# ESP32RobotBoard.net
KiCad netlist of a schematic drawn in Altium Designer
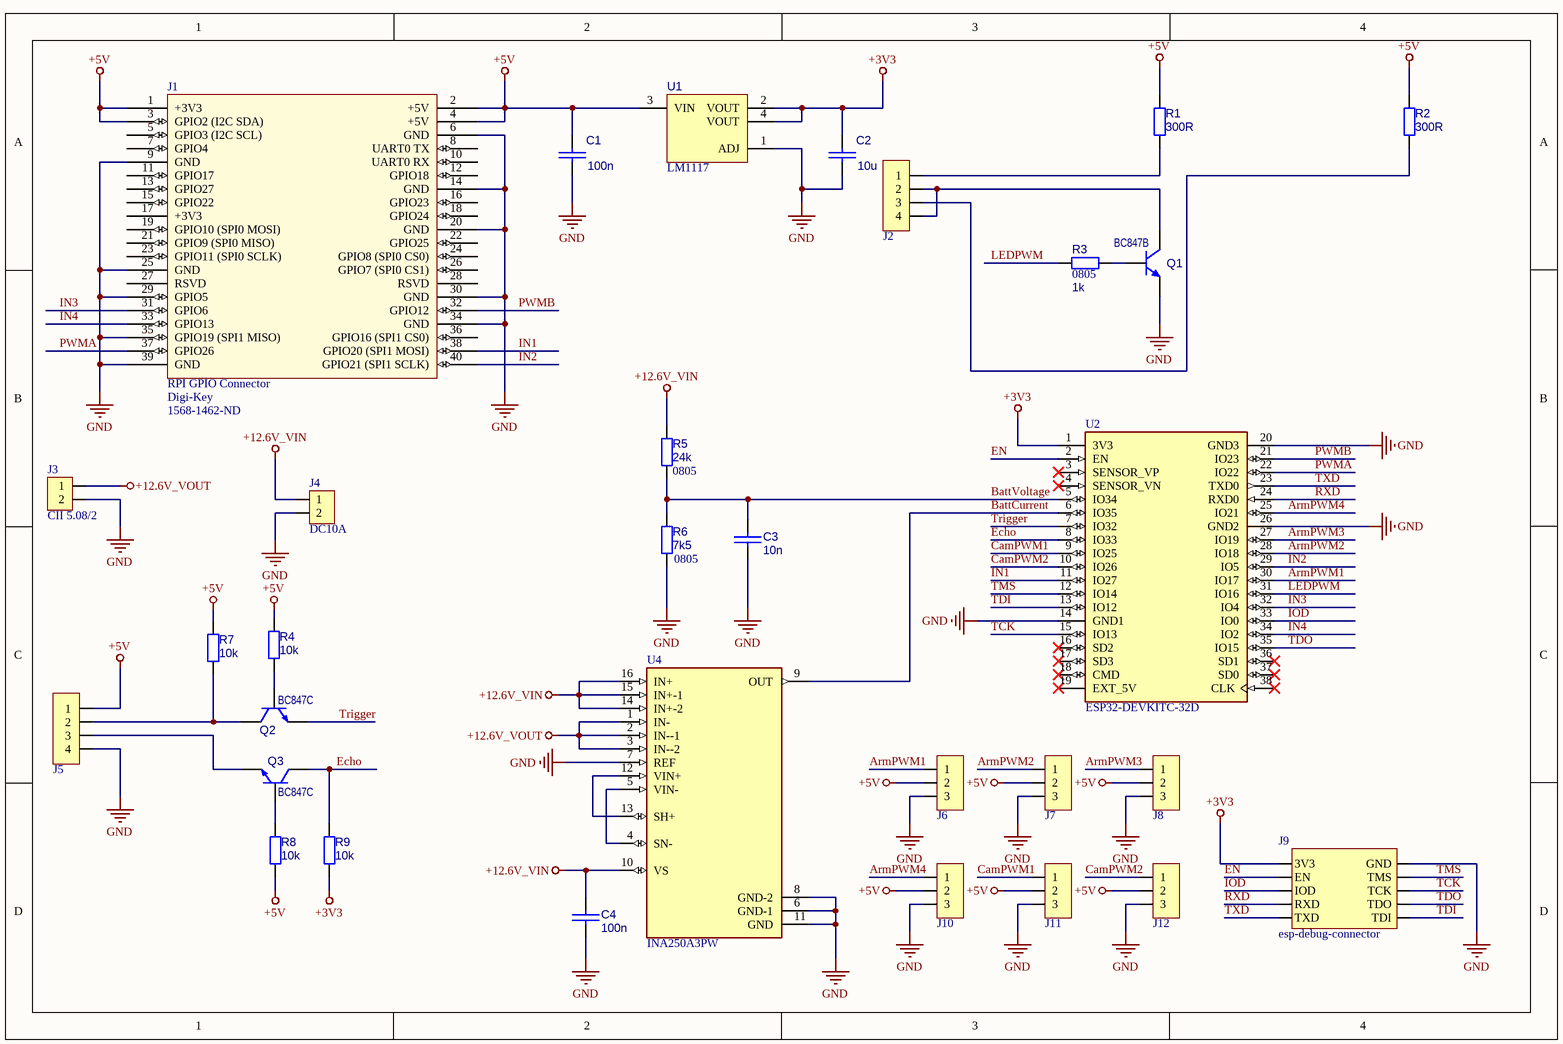
[diagram p0: ESP32RobotBoard.SchDoc]

(export (version "E")
  (design (tool "Eeschema 10.0.6"))
  (components
    (comp (ref "C1")
      (value "100n")
      (footprint "TandariPcbLib:C0805")
      (description "Ceramic Chip Capacitor 0805 size")
      (fields (field (name "VOLTAGE") "50V") (field (name "MANUFACTURER") "NIC COMPONENTS"))
      (libsource (lib "TandariSchlib") (part "Cap100n_50V_0805"))
    )
    (comp (ref "C2")
      (value "10u")
      (footprint "TandariPcbLib:C0805")
      (description "Ceramic Chip Capacitor 0805 size")
      (fields (field (name "VOLTAGE") "10V") (field (name "MANUFACTURER") "NIC"))
      (libsource (lib "TandariSchlib") (part "Cap10u_10V_0805"))
    )
    (comp (ref "C3")
      (value "10n")
      (footprint "TandariPcbLib:C0805")
      (description "Ceramic Chip Capacitor 0805 size")
      (fields (field (name "VOLTAGE") "50V") (field (name "MANUFACTURER") "NIC COMPONENTS"))
      (libsource (lib "TandariSchlib") (part "Cap10n_50V_0805"))
    )
    (comp (ref "C4")
      (value "100n")
      (footprint "TandariPcbLib:C0805")
      (description "Ceramic Chip Capacitor 0805 size")
      (fields (field (name "VOLTAGE") "50V") (field (name "MANUFACTURER") "NIC COMPONENTS"))
      (libsource (lib "TandariSchlib") (part "Cap100n_50V_0805"))
    )
    (comp (ref "J1")
      (value "RPI GPIO Connector")
      (footprint "rpi")
      (description "GPIO Header for Raspberry Pi A+/B+/Pi 2/Pi 3 - 2x20")
      (fields
        (field (name "MANUFACTURER") "SparkFun Electronics")
        (field (name "MANUFACTURER PART NUMBER") "PRT-14017")
        (field (name "SUPPLIER 1") "Digi-Key")
        (field (name "SUPPLIER PART NUMBER 1") "1568-1462-ND")
      )
      (libsource (lib "rpi") (part "rpi connector"))
    )
    (comp (ref "J2")
      (value "BUCHSEHN_1X4")
      (footprint "MKDSN2,5/4-5,08")
      (description "1X4_HEADER")
      (fields (field (name "MANUFACTURER") "E-TEC"))
      (libsource (lib "TandariSchlib") (part "BUCHSEHN_1X4"))
    )
    (comp (ref "J3")
      (value "CII 5.08/2")
      (footprint "MKDSN2,5/2-5,08")
      (fields (field (name "MANUFACTURER") "STELVIO") (field (name "Comment") "2X1Molex"))
      (libsource (lib "TandariSchlib") (part "2X1Molex"))
    )
    (comp (ref "J4")
      (value "DC10A")
      (footprint "DC10A")
      (description "DC 10A connector")
      (fields (field (name "MANUFACTURER") "CLIFF") (field (name "Comment") "CONN_DC10A"))
      (libsource (lib "TandariSchlib") (part "CONN_DC10A"))
    )
    (comp (ref "J5")
      (value "BUCHSEHN_1X4")
      (footprint "MKDSN2,5/4-5,08")
      (description "1X4_HEADER")
      (fields (field (name "MANUFACTURER") "E-TEC"))
      (libsource (lib "TandariSchlib") (part "BUCHSEHN_1X4"))
    )
    (comp (ref "J6")
      (value "BUCHSEHN_1X3")
      (footprint "TandariPcbLib:HEADER_3X1 - male")
      (description "1X3_HEADER")
      (fields (field (name "MANUFACTURER") "E-TEC"))
      (libsource (lib "TandariSchlib") (part "BUCHSEHN_1X3"))
    )
    (comp (ref "J7")
      (value "BUCHSEHN_1X3")
      (footprint "TandariPcbLib:HEADER_3X1 - male")
      (description "1X3_HEADER")
      (fields (field (name "MANUFACTURER") "E-TEC"))
      (libsource (lib "TandariSchlib") (part "BUCHSEHN_1X3"))
    )
    (comp (ref "J8")
      (value "BUCHSEHN_1X3")
      (footprint "TandariPcbLib:HEADER_3X1 - male")
      (description "1X3_HEADER")
      (fields (field (name "MANUFACTURER") "E-TEC"))
      (libsource (lib "TandariSchlib") (part "BUCHSEHN_1X3"))
    )
    (comp (ref "J9")
      (value "esp-debug-connector")
      (footprint "SAMTEC-FTS-105-01-X-DV")
      (fields (field (name "PART NUMBER") "53-04-57"))
      (libsource (lib "TandariSchlib") (part "esp-debug-connector"))
    )
    (comp (ref "J10")
      (value "BUCHSEHN_1X3")
      (footprint "TandariPcbLib:HEADER_3X1 - male")
      (description "1X3_HEADER")
      (fields (field (name "MANUFACTURER") "E-TEC"))
      (libsource (lib "TandariSchlib") (part "BUCHSEHN_1X3"))
    )
    (comp (ref "J11")
      (value "BUCHSEHN_1X3")
      (footprint "TandariPcbLib:HEADER_3X1 - male")
      (description "1X3_HEADER")
      (fields (field (name "MANUFACTURER") "E-TEC"))
      (libsource (lib "TandariSchlib") (part "BUCHSEHN_1X3"))
    )
    (comp (ref "J12")
      (value "BUCHSEHN_1X3")
      (footprint "TandariPcbLib:HEADER_3X1 - male")
      (description "1X3_HEADER")
      (fields (field (name "MANUFACTURER") "E-TEC"))
      (libsource (lib "TandariSchlib") (part "BUCHSEHN_1X3"))
    )
    (comp (ref "Q1")
      (value "NPN")
      (footprint "SOT23-3")
      (description "NPN small-signal 100mA 45V 250mW SOT-23")
      (fields (field (name "MANUFACTURER") "ON Semi") (field (name "PARTNUMBER") "BC847B"))
      (libsource (lib "TandariSchlib") (part "NPN"))
    )
    (comp (ref "Q2")
      (value "BC847C")
      (footprint "TandariPcbLib:SOT23-3")
      (description "NPN Bipolar transistor 100mA 45V UCE")
      (fields (field (name "MANUFACTURER") "NXP") (field (name "Comment") "BC847C_SOT23"))
      (libsource (lib "TandariSchlib") (part "BC847C_SOT23"))
    )
    (comp (ref "Q3")
      (value "BC847C")
      (footprint "TandariPcbLib:SOT23-3")
      (description "NPN Bipolar transistor 100mA 45V UCE")
      (fields (field (name "MANUFACTURER") "NXP") (field (name "Comment") "BC847C_SOT23"))
      (libsource (lib "TandariSchlib") (part "BC847C_SOT23"))
    )
    (comp (ref "R1")
      (value "300R")
      (footprint "TandariPcbLib:R0805")
      (description "Chip Resistor Thick Film")
      (fields (field (name "POWER") "125mW") (field (name "MANUFACTURER") "YAGEO"))
      (libsource (lib "") (part "Res300R_125mW_0805_1"))
    )
    (comp (ref "R2")
      (value "300R")
      (footprint "TandariPcbLib:R0805")
      (description "Chip Resistor Thick Film")
      (fields (field (name "POWER") "125mW") (field (name "MANUFACTURER") "YAGEO"))
      (libsource (lib "TandariSchlib") (part "Res300R_125mW_0805"))
    )
    (comp (ref "R3")
      (value "1k")
      (footprint "TandariPcbLib:R0805")
      (description "Chip Resistor Thick Film")
      (fields
        (field (name "POWER") "125mW")
        (field (name "MANUFACTURER") "YAGEO")
        (field (name "PACKAGE") "0805")
      )
      (libsource (lib "TandariSchlib") (part "Res1k_125mW_0805"))
    )
    (comp (ref "R4")
      (value "10k")
      (footprint "TandariPcbLib:R0805")
      (description "Chip Resistor Thick Film")
      (fields (field (name "POWER") "125mW") (field (name "MANUFACTURER") "YAGEO"))
      (libsource (lib "TandariSchlib") (part "Res10k_125mW_0805"))
    )
    (comp (ref "R5")
      (value "24k")
      (footprint "TandariPcbLib:R0805")
      (description "Chip Resistor Thick Film")
      (fields
        (field (name "POWER") "125mW")
        (field (name "MANUFACTURER") "YAGEO")
        (field (name "PACKAGE") "0805")
      )
      (libsource (lib "TandariSchlib") (part "Res24k_125mW_0805"))
    )
    (comp (ref "R6")
      (value "7k5")
      (footprint "TandariPcbLib:R0805")
      (description "Chip Resistor Thick Film")
      (fields
        (field (name "POWER") "125mW")
        (field (name "MANUFACTURER") "YAGEO")
        (field (name "PACKAGE") "0805")
      )
      (libsource (lib "TandariSchlib") (part "Res7k5_125mW_0805"))
    )
    (comp (ref "R7")
      (value "10k")
      (footprint "TandariPcbLib:R0805")
      (description "Chip Resistor Thick Film")
      (fields (field (name "POWER") "125mW") (field (name "MANUFACTURER") "YAGEO"))
      (libsource (lib "TandariSchlib") (part "Res10k_125mW_0805"))
    )
    (comp (ref "R8")
      (value "10k")
      (footprint "TandariPcbLib:R0805")
      (description "Chip Resistor Thick Film")
      (fields (field (name "POWER") "125mW") (field (name "MANUFACTURER") "YAGEO"))
      (libsource (lib "TandariSchlib") (part "Res10k_125mW_0805"))
    )
    (comp (ref "R9")
      (value "10k")
      (footprint "TandariPcbLib:R0805")
      (description "Chip Resistor Thick Film")
      (fields (field (name "POWER") "125mW") (field (name "MANUFACTURER") "YAGEO"))
      (libsource (lib "TandariSchlib") (part "Res10k_125mW_0805"))
    )
    (comp (ref "U1")
      (value "LM1117")
      (footprint "SOT223")
      (description "15V 800mA adjustable LDO SOT-223")
      (fields (field (name "MANUFACTURER") "National Semiconductor"))
      (libsource (lib "TandariSchlib") (part "LM1117-ADJ"))
    )
    (comp (ref "U2")
      (value "ESP32-DEVKITC-32D")
      (footprint "Espressif_Systems_ESP32-WROOM-32D_MFG")
      (description "EVAL BOARD FOR ESP-WROOM-32")
      (fields (field (name "MF") "Espressif Systems"))
      (libsource (lib "TandariSchlib") (part "ESP32-DEVKITC-32D"))
    )
    (comp (ref "U4")
      (value "INA250A3PW")
      (footprint "TSSOP-16")
      (description "36V, bi-directional, precision current sense amplifier w/int. shunt resistor 16-TSSOP -40 to 125")
      (fields (field (name "MF") "Texas Instruments"))
      (libsource (lib "TandariSchlib") (part "INA250A3PW"))
    )
  )
  (nets
    (net (code "1") (name "+3V3") (class "Default")
      (node (ref "C2") (pin "1") (pinfunction "1_1") (pintype "passive"))
      (node (ref "J9") (pin "1") (pinfunction "3V3_1") (pintype "passive"))
      (node (ref "R9") (pin "1") (pinfunction "1_1") (pintype "passive"))
      (node (ref "U1") (pin "2") (pinfunction "VOUT_2") (pintype "passive"))
      (node (ref "U1") (pin "4") (pinfunction "VOUT_4") (pintype "passive"))
      (node (ref "U2") (pin "1") (pinfunction "3V3_1") (pintype "power_in"))
    )
    (net (code "2") (name "+5V") (class "Default")
      (node (ref "C1") (pin "1") (pinfunction "1_1") (pintype "passive"))
      (node (ref "J1") (pin "1") (pinfunction "+3V3_1") (pintype "power_in"))
      (node (ref "J1") (pin "2") (pinfunction "+5V_2") (pintype "power_in"))
      (node (ref "J1") (pin "3") (pinfunction "GPIO2_(I2C_SDA)_3") (pintype "bidirectional"))
      (node (ref "J1") (pin "4") (pinfunction "+5V_4") (pintype "power_in"))
      (node (ref "J10") (pin "2") (pinfunction "2_2") (pintype "passive"))
      (node (ref "J11") (pin "2") (pinfunction "2_2") (pintype "passive"))
      (node (ref "J12") (pin "2") (pinfunction "2_2") (pintype "passive"))
      (node (ref "J5") (pin "1") (pinfunction "1_1") (pintype "passive"))
      (node (ref "J6") (pin "2") (pinfunction "2_2") (pintype "passive"))
      (node (ref "J7") (pin "2") (pinfunction "2_2") (pintype "passive"))
      (node (ref "J8") (pin "2") (pinfunction "2_2") (pintype "passive"))
      (node (ref "R1") (pin "2") (pinfunction "2_2") (pintype "passive"))
      (node (ref "R2") (pin "2") (pinfunction "2_2") (pintype "passive"))
      (node (ref "R4") (pin "2") (pinfunction "2_2") (pintype "passive"))
      (node (ref "R7") (pin "2") (pinfunction "2_2") (pintype "passive"))
      (node (ref "R8") (pin "1") (pinfunction "1_1") (pintype "passive"))
      (node (ref "U1") (pin "3") (pinfunction "VIN_3") (pintype "passive"))
    )
    (net (code "3") (name "+12.6V_VIN") (class "Default")
      (node (ref "C4") (pin "1") (pinfunction "1_1") (pintype "passive"))
      (node (ref "J4") (pin "1") (pinfunction "1_1") (pintype "passive"))
      (node (ref "R5") (pin "2") (pinfunction "2_2") (pintype "passive"))
      (node (ref "U4") (pin "10") (pinfunction "VS_10") (pintype "bidirectional"))
      (node (ref "U4") (pin "14") (pinfunction "IN+-2_14") (pintype "input"))
      (node (ref "U4") (pin "15") (pinfunction "IN+-1_15") (pintype "input"))
      (node (ref "U4") (pin "16") (pinfunction "IN+_16") (pintype "input"))
    )
    (net (code "4") (name "+12.6V_VOUT") (class "Default")
      (node (ref "J3") (pin "1") (pinfunction "1_1") (pintype "passive"))
      (node (ref "U4") (pin "1") (pinfunction "IN-_1") (pintype "input"))
      (node (ref "U4") (pin "2") (pinfunction "IN--1_2") (pintype "input"))
      (node (ref "U4") (pin "3") (pinfunction "IN--2_3") (pintype "input"))
    )
    (net (code "5") (name "/ArmPWM1") (class "Default")
      (node (ref "J6") (pin "1") (pinfunction "1_1") (pintype "passive"))
      (node (ref "U2") (pin "30") (pinfunction "IO17_30") (pintype "bidirectional"))
    )
    (net (code "6") (name "/ArmPWM2") (class "Default")
      (node (ref "J7") (pin "1") (pinfunction "1_1") (pintype "passive"))
      (node (ref "U2") (pin "28") (pinfunction "IO18_28") (pintype "bidirectional"))
    )
    (net (code "7") (name "/ArmPWM3") (class "Default")
      (node (ref "J8") (pin "1") (pinfunction "1_1") (pintype "passive"))
      (node (ref "U2") (pin "27") (pinfunction "IO19_27") (pintype "bidirectional"))
    )
    (net (code "8") (name "/ArmPWM4") (class "Default")
      (node (ref "J10") (pin "1") (pinfunction "1_1") (pintype "passive"))
      (node (ref "U2") (pin "25") (pinfunction "IO21_25") (pintype "bidirectional"))
    )
    (net (code "9") (name "/BattCurrent") (class "Default")
      (node (ref "U2") (pin "6") (pinfunction "IO35_6") (pintype "bidirectional"))
      (node (ref "U4") (pin "9") (pinfunction "OUT_9") (pintype "output"))
    )
    (net (code "10") (name "/BattVoltage") (class "Default")
      (node (ref "C3") (pin "1") (pinfunction "1_1") (pintype "passive"))
      (node (ref "R5") (pin "1") (pinfunction "1_1") (pintype "passive"))
      (node (ref "R6") (pin "2") (pinfunction "2_2") (pintype "passive"))
      (node (ref "U2") (pin "5") (pinfunction "IO34_5") (pintype "bidirectional"))
    )
    (net (code "11") (name "/CamPWM1") (class "Default")
      (node (ref "J11") (pin "1") (pinfunction "1_1") (pintype "passive"))
      (node (ref "U2") (pin "9") (pinfunction "IO25_9") (pintype "bidirectional"))
    )
    (net (code "12") (name "/CamPWM2") (class "Default")
      (node (ref "J12") (pin "1") (pinfunction "1_1") (pintype "passive"))
      (node (ref "U2") (pin "10") (pinfunction "IO26_10") (pintype "bidirectional"))
    )
    (net (code "13") (name "/EN") (class "Default")
      (node (ref "J9") (pin "3") (pinfunction "EN_3") (pintype "passive"))
      (node (ref "U2") (pin "2") (pinfunction "EN_2") (pintype "input"))
    )
    (net (code "14") (name "/Echo") (class "Default")
      (node (ref "Q3") (pin "3") (pinfunction "C_3") (pintype "passive"))
      (node (ref "R9") (pin "2") (pinfunction "2_2") (pintype "passive"))
      (node (ref "U2") (pin "8") (pinfunction "IO33_8") (pintype "bidirectional"))
    )
    (net (code "15") (name "/IN1") (class "Default")
      (node (ref "J1") (pin "38") (pinfunction "GPIO20_(SPI1_MOSI)_38") (pintype "bidirectional"))
      (node (ref "U2") (pin "11") (pinfunction "IO27_11") (pintype "bidirectional"))
    )
    (net (code "16") (name "/IN2") (class "Default")
      (node (ref "J1") (pin "40") (pinfunction "GPIO21_(SPI1_SCLK)_40") (pintype "bidirectional"))
      (node (ref "U2") (pin "29") (pinfunction "IO5_29") (pintype "bidirectional"))
    )
    (net (code "17") (name "/IN3") (class "Default")
      (node (ref "J1") (pin "31") (pinfunction "GPIO6_31") (pintype "bidirectional"))
      (node (ref "U2") (pin "32") (pinfunction "IO4_32") (pintype "bidirectional"))
    )
    (net (code "18") (name "/IN4") (class "Default")
      (node (ref "J1") (pin "33") (pinfunction "GPIO13_33") (pintype "bidirectional"))
      (node (ref "U2") (pin "34") (pinfunction "IO2_34") (pintype "bidirectional"))
    )
    (net (code "19") (name "/IOD") (class "Default")
      (node (ref "J9") (pin "5") (pinfunction "IOD_5") (pintype "passive"))
      (node (ref "U2") (pin "33") (pinfunction "IO0_33") (pintype "bidirectional"))
    )
    (net (code "20") (name "/LEDPWM") (class "Default")
      (node (ref "R3") (pin "1") (pinfunction "1_1") (pintype "passive"))
      (node (ref "U2") (pin "31") (pinfunction "IO16_31") (pintype "bidirectional"))
    )
    (net (code "21") (name "/PWMA") (class "Default")
      (node (ref "J1") (pin "37") (pinfunction "GPIO26_37") (pintype "bidirectional"))
      (node (ref "U2") (pin "22") (pinfunction "IO22_22") (pintype "bidirectional"))
    )
    (net (code "22") (name "/PWMB") (class "Default")
      (node (ref "J1") (pin "32") (pinfunction "GPIO12_32") (pintype "bidirectional"))
      (node (ref "U2") (pin "21") (pinfunction "IO23_21") (pintype "bidirectional"))
    )
    (net (code "23") (name "/RXD") (class "Default")
      (node (ref "J9") (pin "7") (pinfunction "RXD_7") (pintype "passive"))
      (node (ref "U2") (pin "24") (pinfunction "RXD0_24") (pintype "input"))
    )
    (net (code "24") (name "/TCK") (class "Default")
      (node (ref "J9") (pin "6") (pinfunction "TCK_6") (pintype "passive"))
      (node (ref "U2") (pin "15") (pinfunction "IO13_15") (pintype "bidirectional"))
    )
    (net (code "25") (name "/TDI") (class "Default")
      (node (ref "J9") (pin "10") (pinfunction "TDI_10") (pintype "passive"))
      (node (ref "U2") (pin "13") (pinfunction "IO12_13") (pintype "bidirectional"))
    )
    (net (code "26") (name "/TDO") (class "Default")
      (node (ref "J9") (pin "8") (pinfunction "TDO_8") (pintype "passive"))
      (node (ref "U2") (pin "35") (pinfunction "IO15_35") (pintype "bidirectional"))
    )
    (net (code "27") (name "/TMS") (class "Default")
      (node (ref "J9") (pin "4") (pinfunction "TMS_4") (pintype "passive"))
      (node (ref "U2") (pin "12") (pinfunction "IO14_12") (pintype "bidirectional"))
    )
    (net (code "28") (name "/TXD") (class "Default")
      (node (ref "J9") (pin "9") (pinfunction "TXD_9") (pintype "passive"))
      (node (ref "U2") (pin "23") (pinfunction "TXD0_23") (pintype "output"))
    )
    (net (code "29") (name "/Trigger") (class "Default")
      (node (ref "Q2") (pin "2") (pinfunction "E_2") (pintype "passive"))
      (node (ref "U2") (pin "7") (pinfunction "IO32_7") (pintype "bidirectional"))
    )
    (net (code "30") (name "GND") (class "Default")
      (node (ref "C1") (pin "2") (pinfunction "2_2") (pintype "passive"))
      (node (ref "C2") (pin "2") (pinfunction "2_2") (pintype "passive"))
      (node (ref "C3") (pin "2") (pinfunction "2_2") (pintype "passive"))
      (node (ref "C4") (pin "2") (pinfunction "2_2") (pintype "passive"))
      (node (ref "J1") (pin "14") (pinfunction "GND_14") (pintype "power_in"))
      (node (ref "J1") (pin "20") (pinfunction "GND_20") (pintype "power_in"))
      (node (ref "J1") (pin "25") (pinfunction "GND_25") (pintype "power_in"))
      (node (ref "J1") (pin "29") (pinfunction "GPIO5_29") (pintype "bidirectional"))
      (node (ref "J1") (pin "30") (pinfunction "GND_30") (pintype "power_in"))
      (node (ref "J1") (pin "34") (pinfunction "GND_34") (pintype "passive"))
      (node (ref "J1") (pin "35") (pinfunction "GPIO19_(SPI1_MISO)_35") (pintype "bidirectional"))
      (node (ref "J1") (pin "39") (pinfunction "GND_39") (pintype "power_in"))
      (node (ref "J1") (pin "6") (pinfunction "GND_6") (pintype "power_in"))
      (node (ref "J1") (pin "9") (pinfunction "GND_9") (pintype "power_in"))
      (node (ref "J10") (pin "3") (pinfunction "3_3") (pintype "passive"))
      (node (ref "J11") (pin "3") (pinfunction "3_3") (pintype "passive"))
      (node (ref "J12") (pin "3") (pinfunction "3_3") (pintype "passive"))
      (node (ref "J3") (pin "2") (pinfunction "2_2") (pintype "passive"))
      (node (ref "J4") (pin "2") (pinfunction "2_2") (pintype "passive"))
      (node (ref "J5") (pin "4") (pinfunction "4_4") (pintype "passive"))
      (node (ref "J6") (pin "3") (pinfunction "3_3") (pintype "passive"))
      (node (ref "J7") (pin "3") (pinfunction "3_3") (pintype "passive"))
      (node (ref "J8") (pin "3") (pinfunction "3_3") (pintype "passive"))
      (node (ref "J9") (pin "2") (pinfunction "GND_2") (pintype "passive"))
      (node (ref "Q1") (pin "2") (pinfunction "E_2") (pintype "passive"))
      (node (ref "R6") (pin "1") (pinfunction "1_1") (pintype "passive"))
      (node (ref "U1") (pin "1") (pinfunction "ADJ_1") (pintype "passive"))
      (node (ref "U2") (pin "14") (pinfunction "GND1_14") (pintype "power_in"))
      (node (ref "U2") (pin "20") (pinfunction "GND3_20") (pintype "power_in"))
      (node (ref "U2") (pin "26") (pinfunction "GND2_26") (pintype "power_in"))
      (node (ref "U4") (pin "11") (pinfunction "GND_11") (pintype "power_in"))
      (node (ref "U4") (pin "6") (pinfunction "GND-1_6") (pintype "power_in"))
      (node (ref "U4") (pin "7") (pinfunction "REF_7") (pintype "input"))
      (node (ref "U4") (pin "8") (pinfunction "GND-2_8") (pintype "power_in"))
    )
    (net (code "31") (name "Net-(J2-Pad1)") (class "Default")
      (node (ref "J2") (pin "1") (pinfunction "1_1") (pintype "passive"))
      (node (ref "R1") (pin "1") (pinfunction "1_1") (pintype "passive"))
    )
    (net (code "32") (name "Net-(J2-Pad3)") (class "Default")
      (node (ref "J2") (pin "3") (pinfunction "3_3") (pintype "passive"))
      (node (ref "R2") (pin "1") (pinfunction "1_1") (pintype "passive"))
    )
    (net (code "33") (name "Net-(Q1-B)") (class "Default")
      (node (ref "Q1") (pin "1") (pinfunction "B_1") (pintype "passive"))
      (node (ref "R3") (pin "2") (pinfunction "2_2") (pintype "passive"))
    )
    (net (code "34") (name "Net-(Q1-C)") (class "Default")
      (node (ref "J2") (pin "2") (pinfunction "2_2") (pintype "passive"))
      (node (ref "J2") (pin "4") (pinfunction "4_4") (pintype "passive"))
      (node (ref "Q1") (pin "3") (pinfunction "C_3") (pintype "passive"))
    )
    (net (code "35") (name "Net-(Q2-B)") (class "Default")
      (node (ref "Q2") (pin "1") (pinfunction "B_1") (pintype "passive"))
      (node (ref "R4") (pin "1") (pinfunction "1_1") (pintype "passive"))
    )
    (net (code "36") (name "Net-(Q2-C)") (class "Default")
      (node (ref "J5") (pin "2") (pinfunction "2_2") (pintype "passive"))
      (node (ref "Q2") (pin "3") (pinfunction "C_3") (pintype "passive"))
      (node (ref "R7") (pin "1") (pinfunction "1_1") (pintype "passive"))
    )
    (net (code "37") (name "Net-(Q3-B)") (class "Default")
      (node (ref "Q3") (pin "1") (pinfunction "B_1") (pintype "passive"))
      (node (ref "R8") (pin "2") (pinfunction "2_2") (pintype "passive"))
    )
    (net (code "38") (name "Net-(Q3-E)") (class "Default")
      (node (ref "J5") (pin "3") (pinfunction "3_3") (pintype "passive"))
      (node (ref "Q3") (pin "2") (pinfunction "E_2") (pintype "passive"))
    )
    (net (code "39") (name "Net-(U4-SH+)") (class "Default")
      (node (ref "U4") (pin "12") (pinfunction "VIN+_12") (pintype "input"))
      (node (ref "U4") (pin "13") (pinfunction "SH+_13") (pintype "bidirectional"))
    )
    (net (code "40") (name "Net-(U4-SN-)") (class "Default")
      (node (ref "U4") (pin "4") (pinfunction "SN-_4") (pintype "bidirectional"))
      (node (ref "U4") (pin "5") (pinfunction "VIN-_5") (pintype "input"))
    )
    (net (code "41") (name "unconnected-(J1-+3V3-Pad17)") (class "Default")
      (node (ref "J1") (pin "17") (pinfunction "+3V3_17") (pintype "power_in"))
    )
    (net (code "42") (name "unconnected-(J1-GPIO3_(I2C_SCL)-Pad5)") (class "Default")
      (node (ref "J1") (pin "5") (pinfunction "GPIO3_(I2C_SCL)_5") (pintype "bidirectional"))
    )
    (net (code "43") (name "unconnected-(J1-GPIO4-Pad7)") (class "Default")
      (node (ref "J1") (pin "7") (pinfunction "GPIO4_7") (pintype "bidirectional"))
    )
    (net (code "44") (name "unconnected-(J1-GPIO7_(SPI0_CS1)-Pad26)") (class "Default")
      (node (ref "J1") (pin "26") (pinfunction "GPIO7_(SPI0_CS1)_26") (pintype "bidirectional"))
    )
    (net (code "45") (name "unconnected-(J1-GPIO8_(SPI0_CS0)-Pad24)") (class "Default")
      (node (ref "J1") (pin "24") (pinfunction "GPIO8_(SPI0_CS0)_24") (pintype "bidirectional"))
    )
    (net (code "46") (name "unconnected-(J1-GPIO9_(SPI0_MISO)-Pad21)") (class "Default")
      (node (ref "J1") (pin "21") (pinfunction "GPIO9_(SPI0_MISO)_21") (pintype "bidirectional"))
    )
    (net (code "47") (name "unconnected-(J1-GPIO10_(SPI0_MOSI)-Pad19)") (class "Default")
      (node (ref "J1") (pin "19") (pinfunction "GPIO10_(SPI0_MOSI)_19") (pintype "bidirectional"))
    )
    (net (code "48") (name "unconnected-(J1-GPIO11_(SPI0_SCLK)-Pad23)") (class "Default")
      (node (ref "J1") (pin "23") (pinfunction "GPIO11_(SPI0_SCLK)_23") (pintype "bidirectional"))
    )
    (net (code "49") (name "unconnected-(J1-GPIO16_(SPI1_CS0)-Pad36)") (class "Default")
      (node (ref "J1") (pin "36") (pinfunction "GPIO16_(SPI1_CS0)_36") (pintype "bidirectional"))
    )
    (net (code "50") (name "unconnected-(J1-GPIO17-Pad11)") (class "Default")
      (node (ref "J1") (pin "11") (pinfunction "GPIO17_11") (pintype "bidirectional"))
    )
    (net (code "51") (name "unconnected-(J1-GPIO18-Pad12)") (class "Default")
      (node (ref "J1") (pin "12") (pinfunction "GPIO18_12") (pintype "bidirectional"))
    )
    (net (code "52") (name "unconnected-(J1-GPIO22-Pad15)") (class "Default")
      (node (ref "J1") (pin "15") (pinfunction "GPIO22_15") (pintype "bidirectional"))
    )
    (net (code "53") (name "unconnected-(J1-GPIO23-Pad16)") (class "Default")
      (node (ref "J1") (pin "16") (pinfunction "GPIO23_16") (pintype "bidirectional"))
    )
    (net (code "54") (name "unconnected-(J1-GPIO24-Pad18)") (class "Default")
      (node (ref "J1") (pin "18") (pinfunction "GPIO24_18") (pintype "bidirectional"))
    )
    (net (code "55") (name "unconnected-(J1-GPIO25-Pad22)") (class "Default")
      (node (ref "J1") (pin "22") (pinfunction "GPIO25_22") (pintype "bidirectional"))
    )
    (net (code "56") (name "unconnected-(J1-GPIO27-Pad13)") (class "Default")
      (node (ref "J1") (pin "13") (pinfunction "GPIO27_13") (pintype "bidirectional"))
    )
    (net (code "57") (name "unconnected-(J1-RSVD-Pad27)") (class "Default")
      (node (ref "J1") (pin "27") (pinfunction "RSVD_27") (pintype "passive"))
    )
    (net (code "58") (name "unconnected-(J1-RSVD-Pad28)") (class "Default")
      (node (ref "J1") (pin "28") (pinfunction "RSVD_28") (pintype "passive"))
    )
    (net (code "59") (name "unconnected-(J1-UART0_RX-Pad10)") (class "Default")
      (node (ref "J1") (pin "10") (pinfunction "UART0_RX_10") (pintype "bidirectional"))
    )
    (net (code "60") (name "unconnected-(J1-UART0_TX-Pad8)") (class "Default")
      (node (ref "J1") (pin "8") (pinfunction "UART0_TX_8") (pintype "bidirectional"))
    )
    (net (code "61") (name "unconnected-(U2-CLK-Pad38)") (class "Default")
      (node (ref "U2") (pin "38") (pinfunction "CLK_38") (pintype "input+no_connect"))
    )
    (net (code "62") (name "unconnected-(U2-CMD-Pad18)") (class "Default")
      (node (ref "U2") (pin "18") (pinfunction "CMD_18") (pintype "bidirectional+no_connect"))
    )
    (net (code "63") (name "unconnected-(U2-EXT_5V-Pad19)") (class "Default")
      (node (ref "U2") (pin "19") (pinfunction "EXT_5V_19") (pintype "power_in+no_connect"))
    )
    (net (code "64") (name "unconnected-(U2-SD0-Pad37)") (class "Default")
      (node (ref "U2") (pin "37") (pinfunction "SD0_37") (pintype "bidirectional+no_connect"))
    )
    (net (code "65") (name "unconnected-(U2-SD1-Pad36)") (class "Default")
      (node (ref "U2") (pin "36") (pinfunction "SD1_36") (pintype "bidirectional+no_connect"))
    )
    (net (code "66") (name "unconnected-(U2-SD2-Pad16)") (class "Default")
      (node (ref "U2") (pin "16") (pinfunction "SD2_16") (pintype "bidirectional+no_connect"))
    )
    (net (code "67") (name "unconnected-(U2-SD3-Pad17)") (class "Default")
      (node (ref "U2") (pin "17") (pinfunction "SD3_17") (pintype "bidirectional+no_connect"))
    )
    (net (code "68") (name "unconnected-(U2-SENSOR_VN-Pad4)") (class "Default")
      (node (ref "U2") (pin "4") (pinfunction "SENSOR_VN_4") (pintype "input+no_connect"))
    )
    (net (code "69") (name "unconnected-(U2-SENSOR_VP-Pad3)") (class "Default")
      (node (ref "U2") (pin "3") (pinfunction "SENSOR_VP_3") (pintype "input+no_connect"))
    )
  )
)
